# headstage.net
KiCad netlist of a schematic drawn in EAGLE
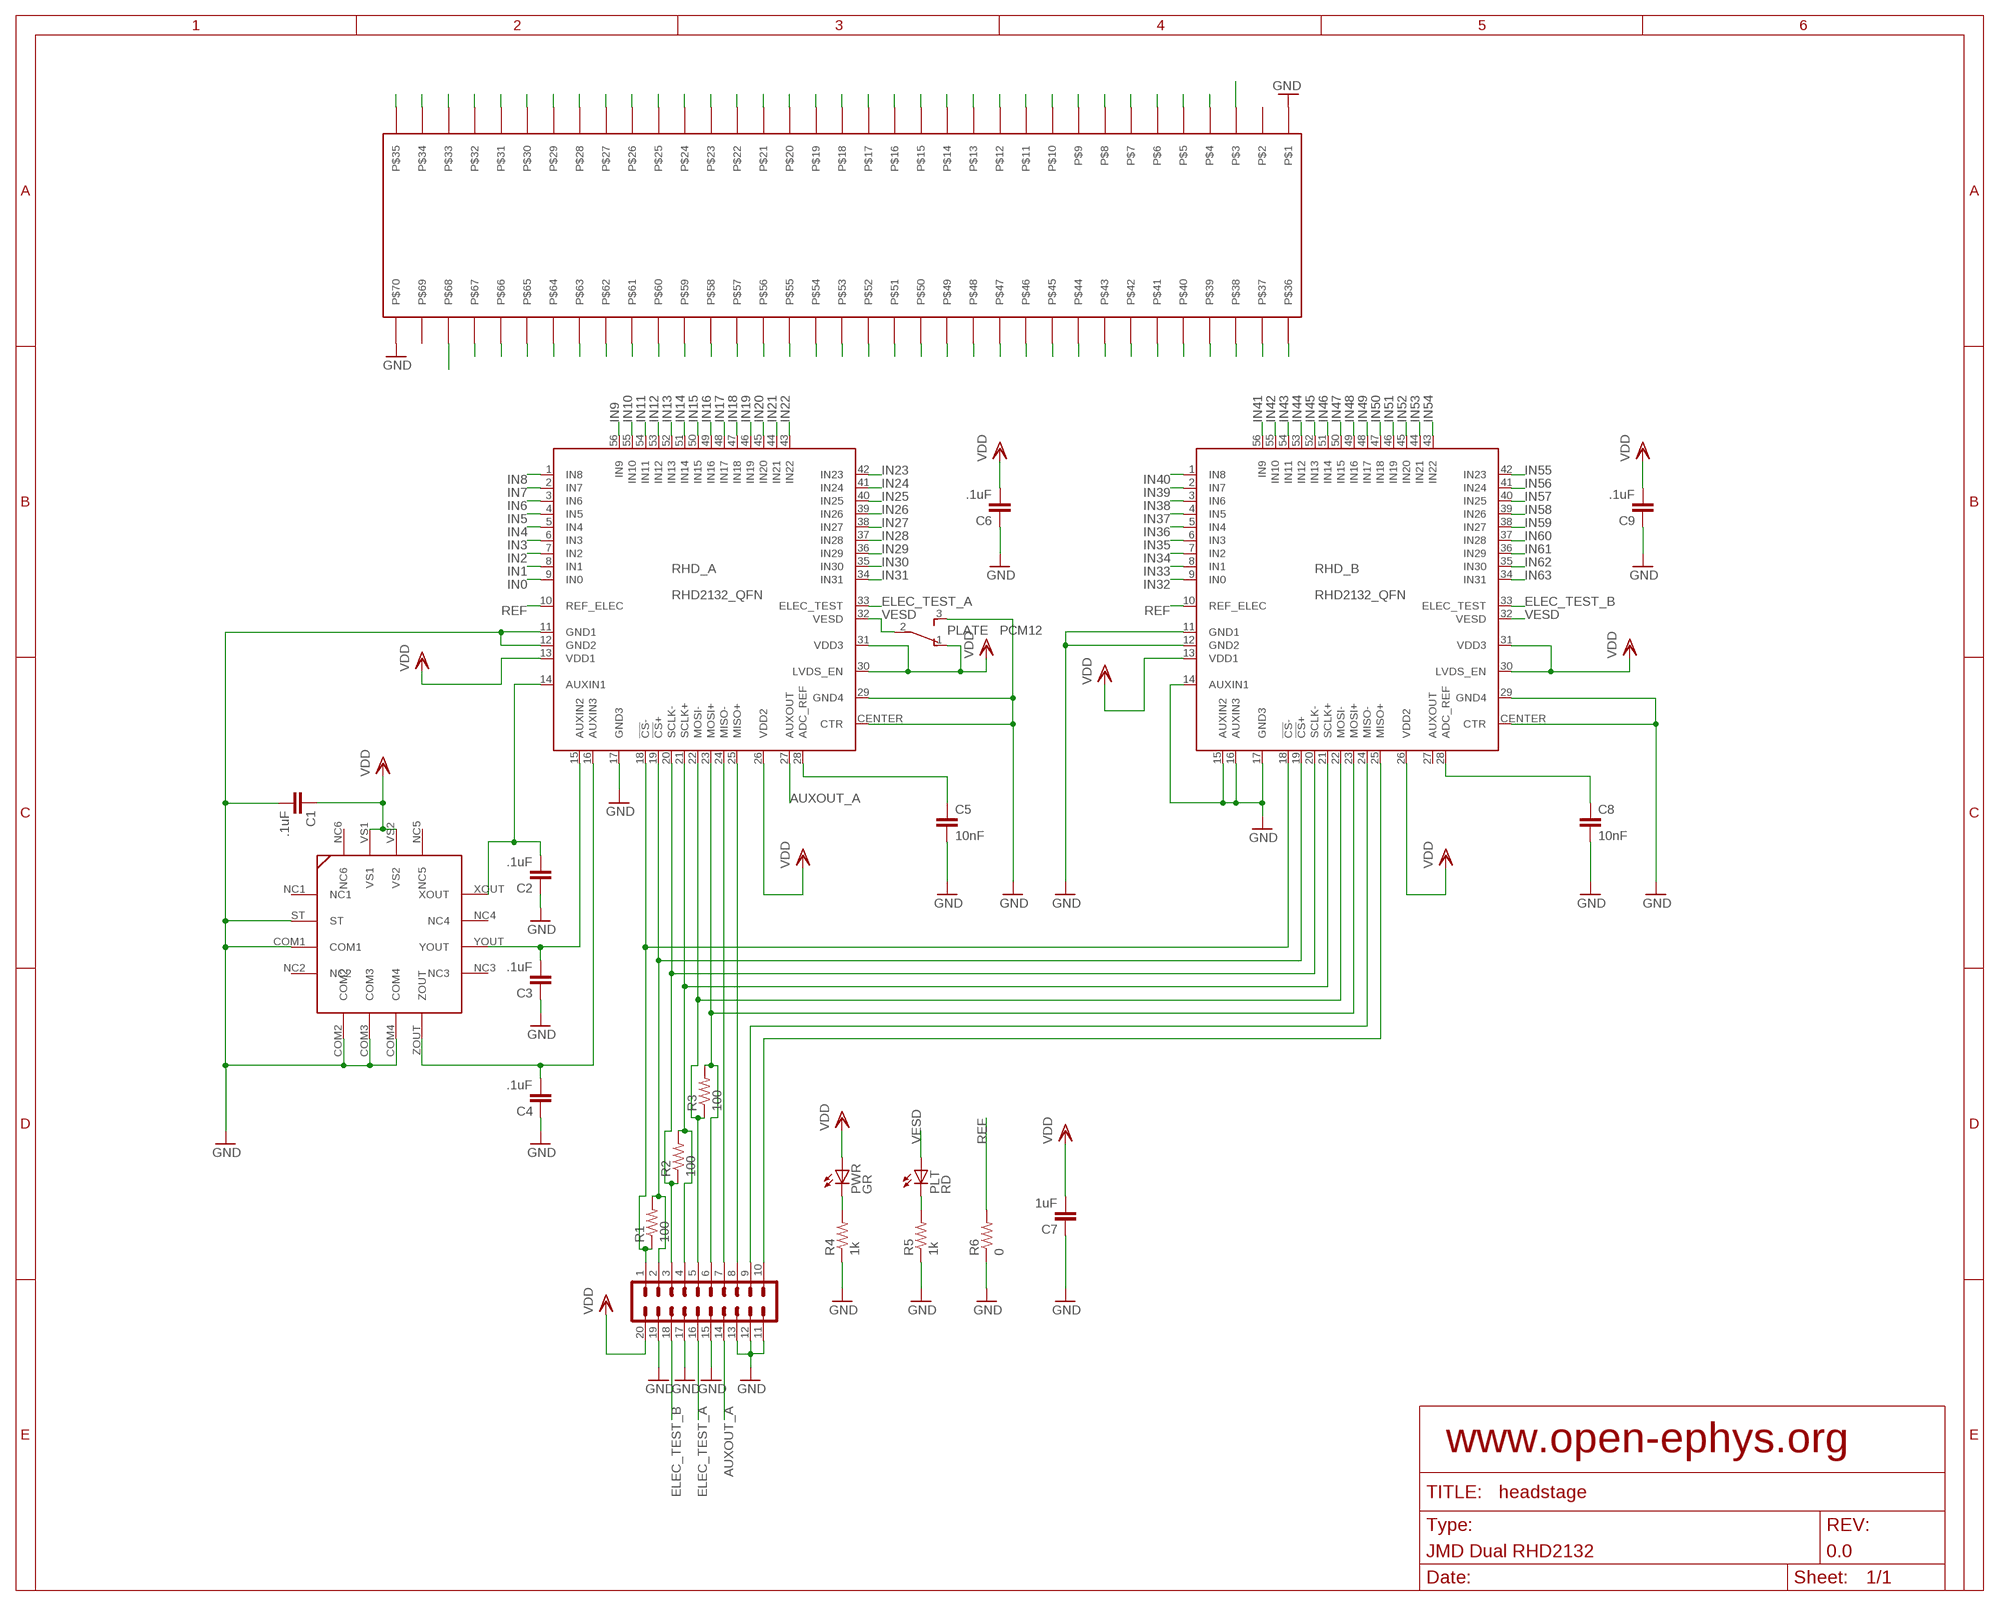
[diagram p0: schematic, sheet 1]

(export (version "E")
  (design (tool "Eeschema 10.0.6"))
  (components
    (comp (ref "C1")
      (value ".1uF")
      (footprint "eagle-import:0402")
      (libsource (lib "eagle-import") (part "C_0402"))
    )
    (comp (ref "C2")
      (value ".1uF")
      (footprint "eagle-import:0402")
      (libsource (lib "eagle-import") (part "C_0402"))
    )
    (comp (ref "C3")
      (value ".1uF")
      (footprint "eagle-import:0402")
      (libsource (lib "eagle-import") (part "C_0402"))
    )
    (comp (ref "C4")
      (value ".1uF")
      (footprint "eagle-import:0402")
      (libsource (lib "eagle-import") (part "C_0402"))
    )
    (comp (ref "C5")
      (value "10nF")
      (footprint "eagle-import:0402")
      (libsource (lib "eagle-import") (part "C_0402"))
    )
    (comp (ref "C6")
      (value ".1uF")
      (footprint "eagle-import:0603")
      (libsource (lib "eagle-import") (part "C_0603"))
    )
    (comp (ref "C7")
      (value "1uF")
      (footprint "eagle-import:0603")
      (libsource (lib "eagle-import") (part "C_0603"))
    )
    (comp (ref "C8")
      (value "10nF")
      (footprint "eagle-import:0402")
      (libsource (lib "eagle-import") (part "C_0402"))
    )
    (comp (ref "C9")
      (value ".1uF")
      (footprint "eagle-import:0603")
      (libsource (lib "eagle-import") (part "C_0603"))
    )
    (comp (ref "OUT")
      (value "JMD")
      (footprint "eagle-import:JMD20-RA")
      (libsource (lib "eagle-import") (part "PINHD-2X10_JMD-RA"))
    )
    (comp (ref "PLATE")
      (value "PCM12")
      (footprint "eagle-import:PCM12")
      (libsource (lib "eagle-import") (part "SPDT_PCM12"))
    )
    (comp (ref "PLT")
      (value "RD")
      (footprint "eagle-import:CHIP-LED0603")
      (libsource (lib "eagle-import") (part "LED_0603"))
    )
    (comp (ref "PWR")
      (value "GR")
      (footprint "eagle-import:CHIP-LED0603")
      (libsource (lib "eagle-import") (part "LED_0603"))
    )
    (comp (ref "R1")
      (value "100")
      (footprint "eagle-import:0402")
      (libsource (lib "eagle-import") (part "R_0402"))
    )
    (comp (ref "R2")
      (value "100")
      (footprint "eagle-import:0402")
      (libsource (lib "eagle-import") (part "R_0402"))
    )
    (comp (ref "R3")
      (value "100")
      (footprint "eagle-import:0402")
      (libsource (lib "eagle-import") (part "R_0402"))
    )
    (comp (ref "R4")
      (value "1k")
      (footprint "eagle-import:0402")
      (libsource (lib "eagle-import") (part "R_0402"))
    )
    (comp (ref "R5")
      (value "1k")
      (footprint "eagle-import:0402")
      (libsource (lib "eagle-import") (part "R_0402"))
    )
    (comp (ref "R6")
      (value "0")
      (footprint "eagle-import:0402")
      (libsource (lib "eagle-import") (part "R_0402"))
    )
    (comp (ref "RHD_A")
      (value "RHD2132_QFN")
      (footprint "eagle-import:QFN56_8_X_8_LARGE")
      (libsource (lib "eagle-import") (part "RHD2132_QFN"))
    )
    (comp (ref "RHD_B")
      (value "RHD2132_QFN")
      (footprint "eagle-import:QFN56_8_X_8_LARGE")
      (libsource (lib "eagle-import") (part "RHD2132_QFN"))
    )
    (comp (ref "U$1")
      (value "HIROSE_DF40_70PIN")
      (footprint "eagle-import:HIROSE_DF40C-70DS")
      (libsource (lib "eagle-import") (part "HIROSE_DF40_70PIN"))
    )
    (comp (ref "U1")
      (value "ADXL335")
      (footprint "eagle-import:ADXL335")
      (libsource (lib "eagle-import") (part "ADXL335"))
    )
  )
  (nets
    (net (code "1") (name "/AUXOUT_A") (class "Default")
      (node (ref "OUT") (pin "14") (pinfunction "14_14") (pintype "bidirectional"))
      (node (ref "RHD_A") (pin "27") (pinfunction "AUXOUT_27") (pintype "tri_state"))
    )
    (net (code "2") (name "/ELEC_TEST_A") (class "Default")
      (node (ref "OUT") (pin "16") (pinfunction "16_16") (pintype "bidirectional"))
      (node (ref "RHD_A") (pin "33") (pinfunction "ELEC_TEST_33") (pintype "input"))
    )
    (net (code "3") (name "/ELEC_TEST_B") (class "Default")
      (node (ref "OUT") (pin "18") (pinfunction "18_18") (pintype "bidirectional"))
      (node (ref "RHD_B") (pin "33") (pinfunction "ELEC_TEST_33") (pintype "input"))
    )
    (net (code "4") (name "/IN0") (class "Default")
      (node (ref "RHD_A") (pin "9") (pinfunction "IN0_9") (pintype "input"))
      (node (ref "U$1") (pin "P$4") (pinfunction "P$4_P$4") (pintype "bidirectional"))
    )
    (net (code "5") (name "/IN1") (class "Default")
      (node (ref "RHD_A") (pin "8") (pinfunction "IN1_8") (pintype "input"))
      (node (ref "U$1") (pin "P$5") (pinfunction "P$5_P$5") (pintype "bidirectional"))
    )
    (net (code "6") (name "/IN2") (class "Default")
      (node (ref "RHD_A") (pin "7") (pinfunction "IN2_7") (pintype "input"))
      (node (ref "U$1") (pin "P$6") (pinfunction "P$6_P$6") (pintype "bidirectional"))
    )
    (net (code "7") (name "/IN3") (class "Default")
      (node (ref "RHD_A") (pin "6") (pinfunction "IN3_6") (pintype "input"))
      (node (ref "U$1") (pin "P$7") (pinfunction "P$7_P$7") (pintype "bidirectional"))
    )
    (net (code "8") (name "/IN4") (class "Default")
      (node (ref "RHD_A") (pin "5") (pinfunction "IN4_5") (pintype "input"))
      (node (ref "U$1") (pin "P$8") (pinfunction "P$8_P$8") (pintype "bidirectional"))
    )
    (net (code "9") (name "/IN5") (class "Default")
      (node (ref "RHD_A") (pin "4") (pinfunction "IN5_4") (pintype "input"))
      (node (ref "U$1") (pin "P$9") (pinfunction "P$9_P$9") (pintype "bidirectional"))
    )
    (net (code "10") (name "/IN6") (class "Default")
      (node (ref "RHD_A") (pin "3") (pinfunction "IN6_3") (pintype "input"))
      (node (ref "U$1") (pin "P$10") (pinfunction "P$10_P$10") (pintype "bidirectional"))
    )
    (net (code "11") (name "/IN7") (class "Default")
      (node (ref "RHD_A") (pin "2") (pinfunction "IN7_2") (pintype "input"))
      (node (ref "U$1") (pin "P$11") (pinfunction "P$11_P$11") (pintype "bidirectional"))
    )
    (net (code "12") (name "/IN8") (class "Default")
      (node (ref "RHD_A") (pin "1") (pinfunction "IN8_1") (pintype "input"))
      (node (ref "U$1") (pin "P$12") (pinfunction "P$12_P$12") (pintype "bidirectional"))
    )
    (net (code "13") (name "/IN9") (class "Default")
      (node (ref "RHD_A") (pin "56") (pinfunction "IN9_56") (pintype "input"))
      (node (ref "U$1") (pin "P$13") (pinfunction "P$13_P$13") (pintype "bidirectional"))
    )
    (net (code "14") (name "/IN10") (class "Default")
      (node (ref "RHD_A") (pin "55") (pinfunction "IN10_55") (pintype "input"))
      (node (ref "U$1") (pin "P$14") (pinfunction "P$14_P$14") (pintype "bidirectional"))
    )
    (net (code "15") (name "/IN11") (class "Default")
      (node (ref "RHD_A") (pin "54") (pinfunction "IN11_54") (pintype "input"))
      (node (ref "U$1") (pin "P$15") (pinfunction "P$15_P$15") (pintype "bidirectional"))
    )
    (net (code "16") (name "/IN12") (class "Default")
      (node (ref "RHD_A") (pin "53") (pinfunction "IN12_53") (pintype "input"))
      (node (ref "U$1") (pin "P$16") (pinfunction "P$16_P$16") (pintype "bidirectional"))
    )
    (net (code "17") (name "/IN13") (class "Default")
      (node (ref "RHD_A") (pin "52") (pinfunction "IN13_52") (pintype "input"))
      (node (ref "U$1") (pin "P$17") (pinfunction "P$17_P$17") (pintype "bidirectional"))
    )
    (net (code "18") (name "/IN14") (class "Default")
      (node (ref "RHD_A") (pin "51") (pinfunction "IN14_51") (pintype "input"))
      (node (ref "U$1") (pin "P$18") (pinfunction "P$18_P$18") (pintype "bidirectional"))
    )
    (net (code "19") (name "/IN15") (class "Default")
      (node (ref "RHD_A") (pin "50") (pinfunction "IN15_50") (pintype "input"))
      (node (ref "U$1") (pin "P$19") (pinfunction "P$19_P$19") (pintype "bidirectional"))
    )
    (net (code "20") (name "/IN16") (class "Default")
      (node (ref "RHD_A") (pin "49") (pinfunction "IN16_49") (pintype "input"))
      (node (ref "U$1") (pin "P$20") (pinfunction "P$20_P$20") (pintype "bidirectional"))
    )
    (net (code "21") (name "/IN17") (class "Default")
      (node (ref "RHD_A") (pin "48") (pinfunction "IN17_48") (pintype "input"))
      (node (ref "U$1") (pin "P$21") (pinfunction "P$21_P$21") (pintype "bidirectional"))
    )
    (net (code "22") (name "/IN18") (class "Default")
      (node (ref "RHD_A") (pin "47") (pinfunction "IN18_47") (pintype "input"))
      (node (ref "U$1") (pin "P$22") (pinfunction "P$22_P$22") (pintype "bidirectional"))
    )
    (net (code "23") (name "/IN19") (class "Default")
      (node (ref "RHD_A") (pin "46") (pinfunction "IN19_46") (pintype "input"))
      (node (ref "U$1") (pin "P$23") (pinfunction "P$23_P$23") (pintype "bidirectional"))
    )
    (net (code "24") (name "/IN20") (class "Default")
      (node (ref "RHD_A") (pin "45") (pinfunction "IN20_45") (pintype "input"))
      (node (ref "U$1") (pin "P$24") (pinfunction "P$24_P$24") (pintype "bidirectional"))
    )
    (net (code "25") (name "/IN21") (class "Default")
      (node (ref "RHD_A") (pin "44") (pinfunction "IN21_44") (pintype "input"))
      (node (ref "U$1") (pin "P$25") (pinfunction "P$25_P$25") (pintype "bidirectional"))
    )
    (net (code "26") (name "/IN22") (class "Default")
      (node (ref "RHD_A") (pin "43") (pinfunction "IN22_43") (pintype "input"))
      (node (ref "U$1") (pin "P$26") (pinfunction "P$26_P$26") (pintype "bidirectional"))
    )
    (net (code "27") (name "/IN23") (class "Default")
      (node (ref "RHD_A") (pin "42") (pinfunction "IN23_42") (pintype "input"))
      (node (ref "U$1") (pin "P$27") (pinfunction "P$27_P$27") (pintype "bidirectional"))
    )
    (net (code "28") (name "/IN24") (class "Default")
      (node (ref "RHD_A") (pin "41") (pinfunction "IN24_41") (pintype "input"))
      (node (ref "U$1") (pin "P$28") (pinfunction "P$28_P$28") (pintype "bidirectional"))
    )
    (net (code "29") (name "/IN25") (class "Default")
      (node (ref "RHD_A") (pin "40") (pinfunction "IN25_40") (pintype "input"))
      (node (ref "U$1") (pin "P$29") (pinfunction "P$29_P$29") (pintype "bidirectional"))
    )
    (net (code "30") (name "/IN26") (class "Default")
      (node (ref "RHD_A") (pin "39") (pinfunction "IN26_39") (pintype "input"))
      (node (ref "U$1") (pin "P$30") (pinfunction "P$30_P$30") (pintype "bidirectional"))
    )
    (net (code "31") (name "/IN27") (class "Default")
      (node (ref "RHD_A") (pin "38") (pinfunction "IN27_38") (pintype "input"))
      (node (ref "U$1") (pin "P$31") (pinfunction "P$31_P$31") (pintype "bidirectional"))
    )
    (net (code "32") (name "/IN28") (class "Default")
      (node (ref "RHD_A") (pin "37") (pinfunction "IN28_37") (pintype "input"))
      (node (ref "U$1") (pin "P$32") (pinfunction "P$32_P$32") (pintype "bidirectional"))
    )
    (net (code "33") (name "/IN29") (class "Default")
      (node (ref "RHD_A") (pin "36") (pinfunction "IN29_36") (pintype "input"))
      (node (ref "U$1") (pin "P$33") (pinfunction "P$33_P$33") (pintype "bidirectional"))
    )
    (net (code "34") (name "/IN30") (class "Default")
      (node (ref "RHD_A") (pin "35") (pinfunction "IN30_35") (pintype "input"))
      (node (ref "U$1") (pin "P$34") (pinfunction "P$34_P$34") (pintype "bidirectional"))
    )
    (net (code "35") (name "/IN31") (class "Default")
      (node (ref "RHD_A") (pin "34") (pinfunction "IN31_34") (pintype "input"))
      (node (ref "U$1") (pin "P$35") (pinfunction "P$35_P$35") (pintype "bidirectional"))
    )
    (net (code "36") (name "/IN32") (class "Default")
      (node (ref "RHD_B") (pin "9") (pinfunction "IN0_9") (pintype "input"))
      (node (ref "U$1") (pin "P$67") (pinfunction "P$67_P$67") (pintype "bidirectional"))
    )
    (net (code "37") (name "/IN33") (class "Default")
      (node (ref "RHD_B") (pin "8") (pinfunction "IN1_8") (pintype "input"))
      (node (ref "U$1") (pin "P$66") (pinfunction "P$66_P$66") (pintype "bidirectional"))
    )
    (net (code "38") (name "/IN34") (class "Default")
      (node (ref "RHD_B") (pin "7") (pinfunction "IN2_7") (pintype "input"))
      (node (ref "U$1") (pin "P$65") (pinfunction "P$65_P$65") (pintype "bidirectional"))
    )
    (net (code "39") (name "/IN35") (class "Default")
      (node (ref "RHD_B") (pin "6") (pinfunction "IN3_6") (pintype "input"))
      (node (ref "U$1") (pin "P$64") (pinfunction "P$64_P$64") (pintype "bidirectional"))
    )
    (net (code "40") (name "/IN36") (class "Default")
      (node (ref "RHD_B") (pin "5") (pinfunction "IN4_5") (pintype "input"))
      (node (ref "U$1") (pin "P$63") (pinfunction "P$63_P$63") (pintype "bidirectional"))
    )
    (net (code "41") (name "/IN37") (class "Default")
      (node (ref "RHD_B") (pin "4") (pinfunction "IN5_4") (pintype "input"))
      (node (ref "U$1") (pin "P$62") (pinfunction "P$62_P$62") (pintype "bidirectional"))
    )
    (net (code "42") (name "/IN38") (class "Default")
      (node (ref "RHD_B") (pin "3") (pinfunction "IN6_3") (pintype "input"))
      (node (ref "U$1") (pin "P$61") (pinfunction "P$61_P$61") (pintype "bidirectional"))
    )
    (net (code "43") (name "/IN39") (class "Default")
      (node (ref "RHD_B") (pin "2") (pinfunction "IN7_2") (pintype "input"))
      (node (ref "U$1") (pin "P$60") (pinfunction "P$60_P$60") (pintype "bidirectional"))
    )
    (net (code "44") (name "/IN40") (class "Default")
      (node (ref "RHD_B") (pin "1") (pinfunction "IN8_1") (pintype "input"))
      (node (ref "U$1") (pin "P$59") (pinfunction "P$59_P$59") (pintype "bidirectional"))
    )
    (net (code "45") (name "/IN41") (class "Default")
      (node (ref "RHD_B") (pin "56") (pinfunction "IN9_56") (pintype "input"))
      (node (ref "U$1") (pin "P$58") (pinfunction "P$58_P$58") (pintype "bidirectional"))
    )
    (net (code "46") (name "/IN42") (class "Default")
      (node (ref "RHD_B") (pin "55") (pinfunction "IN10_55") (pintype "input"))
      (node (ref "U$1") (pin "P$57") (pinfunction "P$57_P$57") (pintype "bidirectional"))
    )
    (net (code "47") (name "/IN43") (class "Default")
      (node (ref "RHD_B") (pin "54") (pinfunction "IN11_54") (pintype "input"))
      (node (ref "U$1") (pin "P$56") (pinfunction "P$56_P$56") (pintype "bidirectional"))
    )
    (net (code "48") (name "/IN44") (class "Default")
      (node (ref "RHD_B") (pin "53") (pinfunction "IN12_53") (pintype "input"))
      (node (ref "U$1") (pin "P$55") (pinfunction "P$55_P$55") (pintype "bidirectional"))
    )
    (net (code "49") (name "/IN45") (class "Default")
      (node (ref "RHD_B") (pin "52") (pinfunction "IN13_52") (pintype "input"))
      (node (ref "U$1") (pin "P$54") (pinfunction "P$54_P$54") (pintype "bidirectional"))
    )
    (net (code "50") (name "/IN46") (class "Default")
      (node (ref "RHD_B") (pin "51") (pinfunction "IN14_51") (pintype "input"))
      (node (ref "U$1") (pin "P$53") (pinfunction "P$53_P$53") (pintype "bidirectional"))
    )
    (net (code "51") (name "/IN47") (class "Default")
      (node (ref "RHD_B") (pin "50") (pinfunction "IN15_50") (pintype "input"))
      (node (ref "U$1") (pin "P$52") (pinfunction "P$52_P$52") (pintype "bidirectional"))
    )
    (net (code "52") (name "/IN48") (class "Default")
      (node (ref "RHD_B") (pin "49") (pinfunction "IN16_49") (pintype "input"))
      (node (ref "U$1") (pin "P$51") (pinfunction "P$51_P$51") (pintype "bidirectional"))
    )
    (net (code "53") (name "/IN49") (class "Default")
      (node (ref "RHD_B") (pin "48") (pinfunction "IN17_48") (pintype "input"))
      (node (ref "U$1") (pin "P$50") (pinfunction "P$50_P$50") (pintype "bidirectional"))
    )
    (net (code "54") (name "/IN50") (class "Default")
      (node (ref "RHD_B") (pin "47") (pinfunction "IN18_47") (pintype "input"))
      (node (ref "U$1") (pin "P$49") (pinfunction "P$49_P$49") (pintype "bidirectional"))
    )
    (net (code "55") (name "/IN51") (class "Default")
      (node (ref "RHD_B") (pin "46") (pinfunction "IN19_46") (pintype "input"))
      (node (ref "U$1") (pin "P$48") (pinfunction "P$48_P$48") (pintype "bidirectional"))
    )
    (net (code "56") (name "/IN52") (class "Default")
      (node (ref "RHD_B") (pin "45") (pinfunction "IN20_45") (pintype "input"))
      (node (ref "U$1") (pin "P$47") (pinfunction "P$47_P$47") (pintype "bidirectional"))
    )
    (net (code "57") (name "/IN53") (class "Default")
      (node (ref "RHD_B") (pin "44") (pinfunction "IN21_44") (pintype "input"))
      (node (ref "U$1") (pin "P$46") (pinfunction "P$46_P$46") (pintype "bidirectional"))
    )
    (net (code "58") (name "/IN54") (class "Default")
      (node (ref "RHD_B") (pin "43") (pinfunction "IN22_43") (pintype "input"))
      (node (ref "U$1") (pin "P$45") (pinfunction "P$45_P$45") (pintype "bidirectional"))
    )
    (net (code "59") (name "/IN55") (class "Default")
      (node (ref "RHD_B") (pin "42") (pinfunction "IN23_42") (pintype "input"))
      (node (ref "U$1") (pin "P$44") (pinfunction "P$44_P$44") (pintype "bidirectional"))
    )
    (net (code "60") (name "/IN56") (class "Default")
      (node (ref "RHD_B") (pin "41") (pinfunction "IN24_41") (pintype "input"))
      (node (ref "U$1") (pin "P$43") (pinfunction "P$43_P$43") (pintype "bidirectional"))
    )
    (net (code "61") (name "/IN57") (class "Default")
      (node (ref "RHD_B") (pin "40") (pinfunction "IN25_40") (pintype "input"))
      (node (ref "U$1") (pin "P$42") (pinfunction "P$42_P$42") (pintype "bidirectional"))
    )
    (net (code "62") (name "/IN58") (class "Default")
      (node (ref "RHD_B") (pin "39") (pinfunction "IN26_39") (pintype "input"))
      (node (ref "U$1") (pin "P$41") (pinfunction "P$41_P$41") (pintype "bidirectional"))
    )
    (net (code "63") (name "/IN59") (class "Default")
      (node (ref "RHD_B") (pin "38") (pinfunction "IN27_38") (pintype "input"))
      (node (ref "U$1") (pin "P$40") (pinfunction "P$40_P$40") (pintype "bidirectional"))
    )
    (net (code "64") (name "/IN60") (class "Default")
      (node (ref "RHD_B") (pin "37") (pinfunction "IN28_37") (pintype "input"))
      (node (ref "U$1") (pin "P$39") (pinfunction "P$39_P$39") (pintype "bidirectional"))
    )
    (net (code "65") (name "/IN61") (class "Default")
      (node (ref "RHD_B") (pin "36") (pinfunction "IN29_36") (pintype "input"))
      (node (ref "U$1") (pin "P$38") (pinfunction "P$38_P$38") (pintype "bidirectional"))
    )
    (net (code "66") (name "/IN62") (class "Default")
      (node (ref "RHD_B") (pin "35") (pinfunction "IN30_35") (pintype "input"))
      (node (ref "U$1") (pin "P$37") (pinfunction "P$37_P$37") (pintype "bidirectional"))
    )
    (net (code "67") (name "/IN63") (class "Default")
      (node (ref "RHD_B") (pin "34") (pinfunction "IN31_34") (pintype "input"))
      (node (ref "U$1") (pin "P$36") (pinfunction "P$36_P$36") (pintype "bidirectional"))
    )
    (net (code "68") (name "/REF") (class "Default")
      (node (ref "R6") (pin "2") (pinfunction "2_2") (pintype "passive"))
      (node (ref "RHD_A") (pin "10") (pinfunction "REF_ELEC_10") (pintype "input"))
      (node (ref "RHD_B") (pin "10") (pinfunction "REF_ELEC_10") (pintype "input"))
      (node (ref "U$1") (pin "P$3") (pinfunction "P$3_P$3") (pintype "bidirectional"))
      (node (ref "U$1") (pin "P$68") (pinfunction "P$68_P$68") (pintype "bidirectional"))
    )
    (net (code "69") (name "/VESD") (class "Default")
      (node (ref "PLATE") (pin "2") (pinfunction "2_2") (pintype "passive"))
      (node (ref "PLT") (pin "A") (pinfunction "A_A") (pintype "passive"))
      (node (ref "RHD_A") (pin "32") (pinfunction "VESD_32") (pintype "power_in"))
      (node (ref "RHD_B") (pin "32") (pinfunction "VESD_32") (pintype "power_in"))
    )
    (net (code "70") (name "GND") (class "Default")
      (node (ref "C1") (pin "2") (pinfunction "2_2") (pintype "passive"))
      (node (ref "C2") (pin "1") (pinfunction "1_1") (pintype "passive"))
      (node (ref "C3") (pin "1") (pinfunction "1_1") (pintype "passive"))
      (node (ref "C4") (pin "1") (pinfunction "1_1") (pintype "passive"))
      (node (ref "C5") (pin "2") (pinfunction "2_2") (pintype "passive"))
      (node (ref "C6") (pin "1") (pinfunction "1_1") (pintype "passive"))
      (node (ref "C7") (pin "1") (pinfunction "1_1") (pintype "passive"))
      (node (ref "C8") (pin "2") (pinfunction "2_2") (pintype "passive"))
      (node (ref "C9") (pin "1") (pinfunction "1_1") (pintype "passive"))
      (node (ref "OUT") (pin "11") (pinfunction "11_11") (pintype "bidirectional"))
      (node (ref "OUT") (pin "12") (pinfunction "12_12") (pintype "bidirectional"))
      (node (ref "OUT") (pin "13") (pinfunction "13_13") (pintype "bidirectional"))
      (node (ref "OUT") (pin "15") (pinfunction "15_15") (pintype "bidirectional"))
      (node (ref "OUT") (pin "17") (pinfunction "17_17") (pintype "bidirectional"))
      (node (ref "OUT") (pin "19") (pinfunction "19_19") (pintype "bidirectional"))
      (node (ref "PLATE") (pin "3") (pinfunction "3_3") (pintype "passive"))
      (node (ref "R4") (pin "1") (pinfunction "1_1") (pintype "passive"))
      (node (ref "R5") (pin "1") (pinfunction "1_1") (pintype "passive"))
      (node (ref "R6") (pin "1") (pinfunction "1_1") (pintype "passive"))
      (node (ref "RHD_A") (pin "11") (pinfunction "GND1_11") (pintype "power_in"))
      (node (ref "RHD_A") (pin "12") (pinfunction "GND2_12") (pintype "power_in"))
      (node (ref "RHD_A") (pin "17") (pinfunction "GND3_17") (pintype "power_in"))
      (node (ref "RHD_A") (pin "29") (pinfunction "GND4_29") (pintype "power_in"))
      (node (ref "RHD_A") (pin "CENTER") (pinfunction "CTR_CENTER") (pintype "power_in"))
      (node (ref "RHD_B") (pin "11") (pinfunction "GND1_11") (pintype "power_in"))
      (node (ref "RHD_B") (pin "12") (pinfunction "GND2_12") (pintype "power_in"))
      (node (ref "RHD_B") (pin "14") (pinfunction "AUXIN1_14") (pintype "input"))
      (node (ref "RHD_B") (pin "15") (pinfunction "AUXIN2_15") (pintype "input"))
      (node (ref "RHD_B") (pin "16") (pinfunction "AUXIN3_16") (pintype "input"))
      (node (ref "RHD_B") (pin "17") (pinfunction "GND3_17") (pintype "power_in"))
      (node (ref "RHD_B") (pin "29") (pinfunction "GND4_29") (pintype "power_in"))
      (node (ref "RHD_B") (pin "CENTER") (pinfunction "CTR_CENTER") (pintype "power_in"))
      (node (ref "U$1") (pin "P$1") (pinfunction "P$1_P$1") (pintype "bidirectional"))
      (node (ref "U$1") (pin "P$70") (pinfunction "P$70_P$70") (pintype "bidirectional"))
      (node (ref "U1") (pin "COM1") (pinfunction "COM1_COM1") (pintype "bidirectional"))
      (node (ref "U1") (pin "COM2") (pinfunction "COM2_COM2") (pintype "bidirectional"))
      (node (ref "U1") (pin "COM3") (pinfunction "COM3_COM3") (pintype "bidirectional"))
      (node (ref "U1") (pin "COM4") (pinfunction "COM4_COM4") (pintype "bidirectional"))
      (node (ref "U1") (pin "ST") (pinfunction "ST_ST") (pintype "bidirectional"))
    )
    (net (code "71") (name "Net-(PLT-PadC)") (class "Default")
      (node (ref "PLT") (pin "C") (pinfunction "C_C") (pintype "passive"))
      (node (ref "R5") (pin "2") (pinfunction "2_2") (pintype "passive"))
    )
    (net (code "72") (name "Net-(PWR-PadC)") (class "Default")
      (node (ref "PWR") (pin "C") (pinfunction "C_C") (pintype "passive"))
      (node (ref "R4") (pin "2") (pinfunction "2_2") (pintype "passive"))
    )
    (net (code "73") (name "Net-(RHD_A-ADC_REF)") (class "Default")
      (node (ref "C5") (pin "1") (pinfunction "1_1") (pintype "passive"))
      (node (ref "RHD_A") (pin "28") (pinfunction "ADC_REF_28") (pintype "passive"))
    )
    (net (code "74") (name "Net-(RHD_A-AUXIN1)") (class "Default")
      (node (ref "C2") (pin "2") (pinfunction "2_2") (pintype "passive"))
      (node (ref "RHD_A") (pin "14") (pinfunction "AUXIN1_14") (pintype "input"))
      (node (ref "U1") (pin "XOUT") (pinfunction "XOUT_XOUT") (pintype "bidirectional"))
    )
    (net (code "75") (name "Net-(RHD_A-AUXIN2)") (class "Default")
      (node (ref "C3") (pin "2") (pinfunction "2_2") (pintype "passive"))
      (node (ref "RHD_A") (pin "15") (pinfunction "AUXIN2_15") (pintype "input"))
      (node (ref "U1") (pin "YOUT") (pinfunction "YOUT_YOUT") (pintype "bidirectional"))
    )
    (net (code "76") (name "Net-(RHD_A-AUXIN3)") (class "Default")
      (node (ref "C4") (pin "2") (pinfunction "2_2") (pintype "passive"))
      (node (ref "RHD_A") (pin "16") (pinfunction "AUXIN3_16") (pintype "input"))
      (node (ref "U1") (pin "ZOUT") (pinfunction "ZOUT_ZOUT") (pintype "bidirectional"))
    )
    (net (code "77") (name "Net-(RHD_A-MISO+)") (class "Default")
      (node (ref "OUT") (pin "8") (pinfunction "8_8") (pintype "bidirectional"))
      (node (ref "RHD_A") (pin "25") (pinfunction "MISO+_25") (pintype "output"))
    )
    (net (code "78") (name "Net-(RHD_A-MISO-)") (class "Default")
      (node (ref "OUT") (pin "7") (pinfunction "7_7") (pintype "bidirectional"))
      (node (ref "RHD_A") (pin "24") (pinfunction "MISO-_24") (pintype "output"))
    )
    (net (code "79") (name "Net-(RHD_A-MOSI+)") (class "Default")
      (node (ref "OUT") (pin "6") (pinfunction "6_6") (pintype "bidirectional"))
      (node (ref "R3") (pin "2") (pinfunction "2_2") (pintype "passive"))
      (node (ref "RHD_A") (pin "23") (pinfunction "MOSI+_23") (pintype "input"))
      (node (ref "RHD_B") (pin "23") (pinfunction "MOSI+_23") (pintype "input"))
    )
    (net (code "80") (name "Net-(RHD_A-MOSI-)") (class "Default")
      (node (ref "OUT") (pin "5") (pinfunction "5_5") (pintype "bidirectional"))
      (node (ref "R3") (pin "1") (pinfunction "1_1") (pintype "passive"))
      (node (ref "RHD_A") (pin "22") (pinfunction "MOSI-_22") (pintype "input"))
      (node (ref "RHD_B") (pin "22") (pinfunction "MOSI-_22") (pintype "input"))
    )
    (net (code "81") (name "Net-(RHD_A-SCLK+)") (class "Default")
      (node (ref "OUT") (pin "4") (pinfunction "4_4") (pintype "bidirectional"))
      (node (ref "R2") (pin "2") (pinfunction "2_2") (pintype "passive"))
      (node (ref "RHD_A") (pin "21") (pinfunction "SCLK+_21") (pintype "input"))
      (node (ref "RHD_B") (pin "21") (pinfunction "SCLK+_21") (pintype "input"))
    )
    (net (code "82") (name "Net-(RHD_A-SCLK-)") (class "Default")
      (node (ref "OUT") (pin "3") (pinfunction "3_3") (pintype "bidirectional"))
      (node (ref "R2") (pin "1") (pinfunction "1_1") (pintype "passive"))
      (node (ref "RHD_A") (pin "20") (pinfunction "SCLK-_20") (pintype "input"))
      (node (ref "RHD_B") (pin "20") (pinfunction "SCLK-_20") (pintype "input"))
    )
    (net (code "83") (name "Net-(RHD_A-~{CS}+)") (class "Default")
      (node (ref "OUT") (pin "2") (pinfunction "2_2") (pintype "bidirectional"))
      (node (ref "R1") (pin "2") (pinfunction "2_2") (pintype "passive"))
      (node (ref "RHD_A") (pin "19") (pinfunction "~{CS}+_19") (pintype "input"))
      (node (ref "RHD_B") (pin "19") (pinfunction "~{CS}+_19") (pintype "input"))
    )
    (net (code "84") (name "Net-(RHD_A-~{CS}-)") (class "Default")
      (node (ref "OUT") (pin "1") (pinfunction "1_1") (pintype "bidirectional"))
      (node (ref "R1") (pin "1") (pinfunction "1_1") (pintype "passive"))
      (node (ref "RHD_A") (pin "18") (pinfunction "~{CS}-_18") (pintype "input"))
      (node (ref "RHD_B") (pin "18") (pinfunction "~{CS}-_18") (pintype "input"))
    )
    (net (code "85") (name "Net-(RHD_B-ADC_REF)") (class "Default")
      (node (ref "C8") (pin "1") (pinfunction "1_1") (pintype "passive"))
      (node (ref "RHD_B") (pin "28") (pinfunction "ADC_REF_28") (pintype "passive"))
    )
    (net (code "86") (name "Net-(RHD_B-MISO+)") (class "Default")
      (node (ref "OUT") (pin "10") (pinfunction "10_10") (pintype "bidirectional"))
      (node (ref "RHD_B") (pin "25") (pinfunction "MISO+_25") (pintype "output"))
    )
    (net (code "87") (name "Net-(RHD_B-MISO-)") (class "Default")
      (node (ref "OUT") (pin "9") (pinfunction "9_9") (pintype "bidirectional"))
      (node (ref "RHD_B") (pin "24") (pinfunction "MISO-_24") (pintype "output"))
    )
    (net (code "88") (name "VDD") (class "Default")
      (node (ref "C1") (pin "1") (pinfunction "1_1") (pintype "passive"))
      (node (ref "C6") (pin "2") (pinfunction "2_2") (pintype "passive"))
      (node (ref "C7") (pin "2") (pinfunction "2_2") (pintype "passive"))
      (node (ref "C9") (pin "2") (pinfunction "2_2") (pintype "passive"))
      (node (ref "OUT") (pin "20") (pinfunction "20_20") (pintype "bidirectional"))
      (node (ref "PLATE") (pin "1") (pinfunction "1_1") (pintype "passive"))
      (node (ref "PWR") (pin "A") (pinfunction "A_A") (pintype "passive"))
      (node (ref "RHD_A") (pin "13") (pinfunction "VDD1_13") (pintype "power_in"))
      (node (ref "RHD_A") (pin "26") (pinfunction "VDD2_26") (pintype "power_in"))
      (node (ref "RHD_A") (pin "30") (pinfunction "LVDS_EN_30") (pintype "input"))
      (node (ref "RHD_A") (pin "31") (pinfunction "VDD3_31") (pintype "power_in"))
      (node (ref "RHD_B") (pin "13") (pinfunction "VDD1_13") (pintype "power_in"))
      (node (ref "RHD_B") (pin "26") (pinfunction "VDD2_26") (pintype "power_in"))
      (node (ref "RHD_B") (pin "30") (pinfunction "LVDS_EN_30") (pintype "input"))
      (node (ref "RHD_B") (pin "31") (pinfunction "VDD3_31") (pintype "power_in"))
      (node (ref "U1") (pin "VS1") (pinfunction "VS1_VS1") (pintype "bidirectional"))
      (node (ref "U1") (pin "VS2") (pinfunction "VS2_VS2") (pintype "bidirectional"))
    )
    (net (code "89") (name "unconnected-(RHD_B-AUXOUT-Pad27)") (class "Default")
      (node (ref "RHD_B") (pin "27") (pinfunction "AUXOUT_27") (pintype "tri_state"))
    )
    (net (code "90") (name "unconnected-(U$1-PadP$2)") (class "Default")
      (node (ref "U$1") (pin "P$2") (pinfunction "P$2_P$2") (pintype "bidirectional"))
    )
    (net (code "91") (name "unconnected-(U$1-PadP$69)") (class "Default")
      (node (ref "U$1") (pin "P$69") (pinfunction "P$69_P$69") (pintype "bidirectional"))
    )
    (net (code "92") (name "unconnected-(U1-PadNC1)") (class "Default")
      (node (ref "U1") (pin "NC1") (pinfunction "NC1_NC1") (pintype "bidirectional"))
    )
    (net (code "93") (name "unconnected-(U1-PadNC2)") (class "Default")
      (node (ref "U1") (pin "NC2") (pinfunction "NC2_NC2") (pintype "bidirectional"))
    )
    (net (code "94") (name "unconnected-(U1-PadNC3)") (class "Default")
      (node (ref "U1") (pin "NC3") (pinfunction "NC3_NC3") (pintype "bidirectional"))
    )
    (net (code "95") (name "unconnected-(U1-PadNC4)") (class "Default")
      (node (ref "U1") (pin "NC4") (pinfunction "NC4_NC4") (pintype "bidirectional"))
    )
    (net (code "96") (name "unconnected-(U1-PadNC5)") (class "Default")
      (node (ref "U1") (pin "NC5") (pinfunction "NC5_NC5") (pintype "bidirectional"))
    )
    (net (code "97") (name "unconnected-(U1-PadNC6)") (class "Default")
      (node (ref "U1") (pin "NC6") (pinfunction "NC6_NC6") (pintype "bidirectional"))
    )
  )
)
